# design.net
KiCad netlist of a schematic drawn in Altium Designer
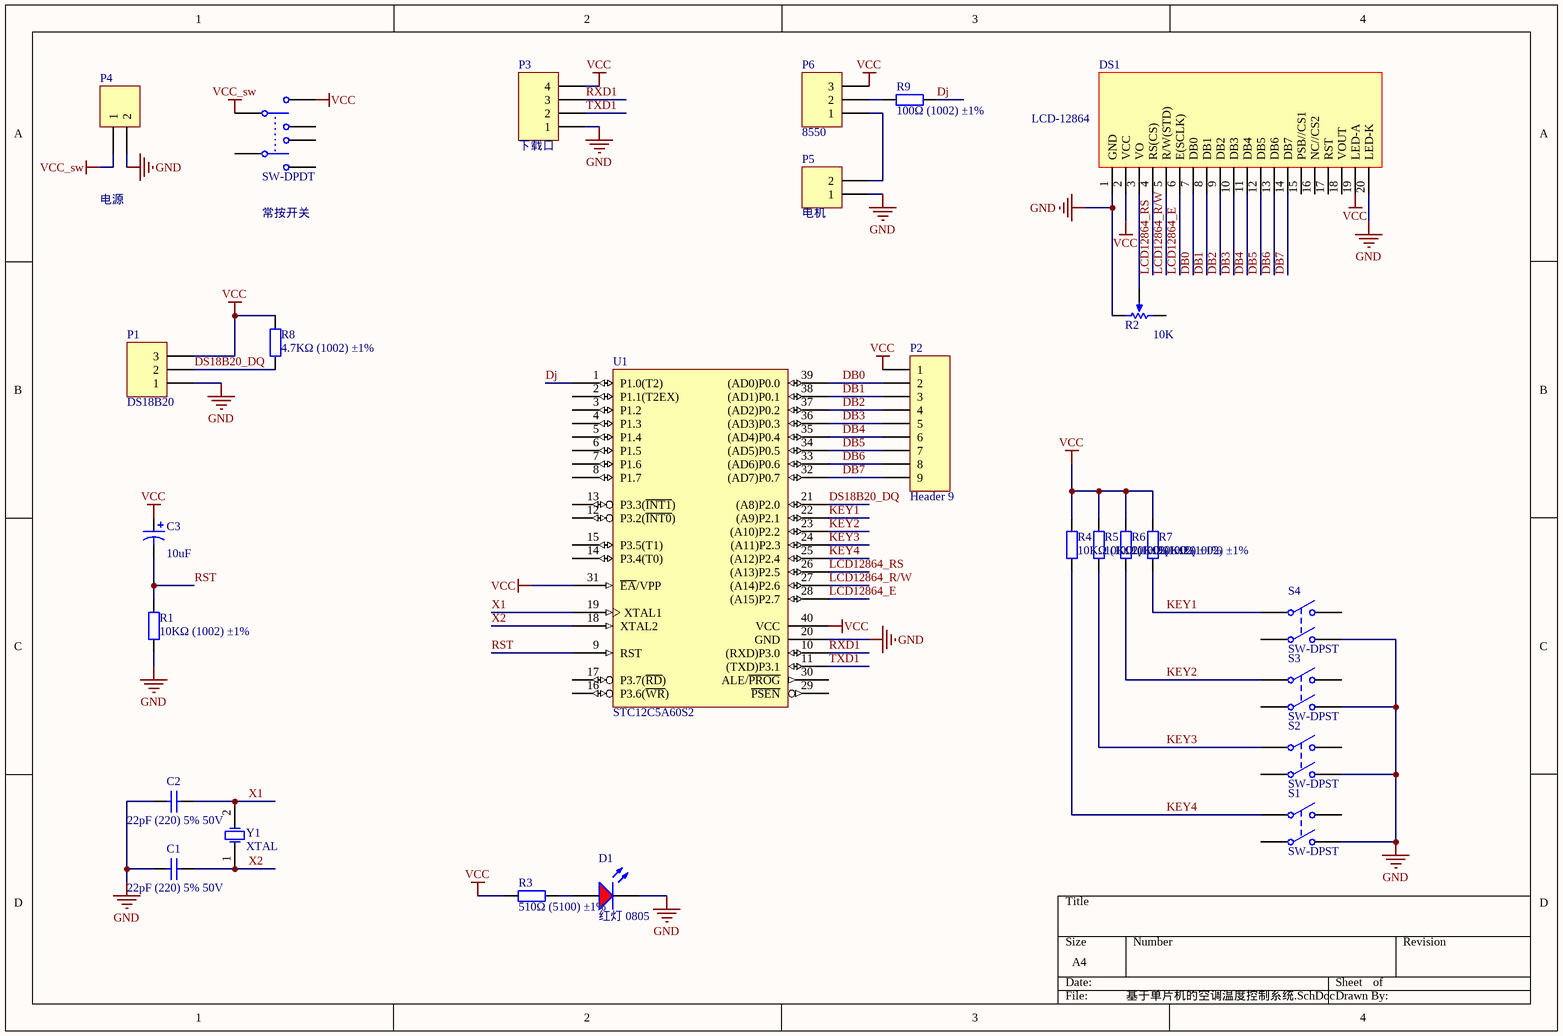
[diagram p0: 基于单片机的空调温度控制系统.SchDoc]

(export (version "E")
  (design (tool "Eeschema 10.0.6"))
  (components
    (comp (ref "C1")
      (value "22pF (220) 5% 50V")
      (footprint "LC-0805_C")
      (description "贴片电容")
      (libsource (lib "Miscellaneous Devices LC") (part "0805 22pF (220) 5% 50V"))
    )
    (comp (ref "C2")
      (value "22pF (220) 5% 50V")
      (footprint "LC-0805_C")
      (description "贴片电容")
      (libsource (lib "Miscellaneous Devices LC") (part "0805 22pF (220) 5% 50V"))
    )
    (comp (ref "C3")
      (value "10uF")
      (footprint "RB.2.5/.6.3mm")
      (description "Polarized Capacitor (Radial)")
      (fields (field (name "Comment") "Cap Pol1") (field (name "PUBLISHER") "Altium Limited"))
      (libsource (lib "Miscellaneous Devices") (part "Cap Pol1"))
    )
    (comp (ref "D1")
      (value "红灯 0805")
      (footprint "LC-0805_LED_S1")
      (description "发光二极管")
      (libsource (lib "Miscellaneous Devices LC") (part "0805 红灯"))
    )
    (comp (ref "DS1")
      (value "LCD-12864")
      (footprint "LCD-12864")
      (description "带//不带字库")
      (libsource (lib "个人") (part "LCD-12864"))
    )
    (comp (ref "P1")
      (value "DS18B20")
      (footprint "HDR1X3")
      (description "Header, 3-Pin")
      (fields (field (name "PUBLISHER") "Altium Limited"))
      (libsource (lib "Miscellaneous Connectors") (part "Header 3"))
    )
    (comp (ref "P2")
      (value "Header 9")
      (footprint "HDR1X9")
      (description "Header, 9-Pin")
      (fields (field (name "PUBLISHER") "Altium Limited"))
      (libsource (lib "Miscellaneous Connectors") (part "Header 9"))
    )
    (comp (ref "P3")
      (value "下载口")
      (footprint "HDR1X4")
      (description "Header, 4-Pin")
      (fields (field (name "PUBLISHER") "Altium Limited"))
      (libsource (lib "Miscellaneous Connectors") (part "Header 4"))
    )
    (comp (ref "P4")
      (value "电源")
      (footprint "DC插座")
      (description "Header, 2-Pin")
      (fields (field (name "PUBLISHER") "Altium Limited"))
      (libsource (lib "Miscellaneous Connectors") (part "Header 2"))
    )
    (comp (ref "P5")
      (value "电机")
      (footprint "HDR1X2")
      (description "Header, 2-Pin")
      (fields (field (name "PUBLISHER") "Altium Limited"))
      (libsource (lib "") (part "Header 2_1"))
    )
    (comp (ref "P6")
      (value "8550")
      (footprint "HDR1X3")
      (description "Header, 3-Pin")
      (fields (field (name "PUBLISHER") "Altium Limited"))
      (libsource (lib "Miscellaneous Connectors") (part "Header 3"))
    )
    (comp (ref "R1")
      (value "10KΩ (1002) ±1%")
      (footprint "LC-0805_R")
      (description "贴片电阻")
      (libsource (lib "Miscellaneous Devices LC") (part "0805 10KΩ (1002) 1%"))
    )
    (comp (ref "R2")
      (value "10K")
      (footprint "VR5")
      (description "Potentiometer")
      (fields (field (name "Comment") "Pot") (field (name "PUBLISHER") "Altium Limited"))
      (libsource (lib "Miscellaneous Devices") (part "RPot"))
    )
    (comp (ref "R3")
      (value "510Ω (5100) ±1%")
      (footprint "LC-0805_R")
      (description "贴片电阻")
      (libsource (lib "Miscellaneous Devices LC") (part "0805 510Ω (5100) 1%"))
    )
    (comp (ref "R4")
      (value "10KΩ (1002) ±1%")
      (footprint "LC-0805_R")
      (description "贴片电阻")
      (libsource (lib "Miscellaneous Devices LC") (part "0805 10KΩ (1002) 1%"))
    )
    (comp (ref "R5")
      (value "10KΩ (1002) ±1%")
      (footprint "LC-0805_R")
      (description "贴片电阻")
      (libsource (lib "Miscellaneous Devices LC") (part "0805 10KΩ (1002) 1%"))
    )
    (comp (ref "R6")
      (value "10KΩ (1002) ±1%")
      (footprint "LC-0805_R")
      (description "贴片电阻")
      (libsource (lib "Miscellaneous Devices LC") (part "0805 10KΩ (1002) 1%"))
    )
    (comp (ref "R7")
      (value "10KΩ (1002) ±1%")
      (footprint "LC-0805_R")
      (description "贴片电阻")
      (libsource (lib "Miscellaneous Devices LC") (part "0805 10KΩ (1002) 1%"))
    )
    (comp (ref "R8")
      (value "4.7KΩ (1002) ±1%")
      (footprint "LC-0805_R")
      (description "贴片电阻")
      (libsource (lib "Miscellaneous Devices LC") (part "0805 10KΩ (1002) 1%"))
    )
    (comp (ref "R9")
      (value "100Ω (1002) ±1%")
      (footprint "LC-0805_R")
      (description "贴片电阻")
      (libsource (lib "") (part "0805 10KΩ (1002) 1%_1"))
    )
    (comp (ref "S1")
      (value "SW-DPST")
      (footprint "Switch6*6")
      (description "Double-Pole, Single-Throw Switch")
      (fields (field (name "PUBLISHER") "Altium Limited"))
      (libsource (lib "Miscellaneous Devices") (part "SW-DPST"))
    )
    (comp (ref "S2")
      (value "SW-DPST")
      (footprint "Switch6*6")
      (description "Double-Pole, Single-Throw Switch")
      (fields (field (name "PUBLISHER") "Altium Limited"))
      (libsource (lib "Miscellaneous Devices") (part "SW-DPST"))
    )
    (comp (ref "S3")
      (value "SW-DPST")
      (footprint "Switch6*6")
      (description "Double-Pole, Single-Throw Switch")
      (fields (field (name "PUBLISHER") "Altium Limited"))
      (libsource (lib "Miscellaneous Devices") (part "SW-DPST"))
    )
    (comp (ref "S4")
      (value "SW-DPST")
      (footprint "Switch6*6")
      (description "Double-Pole, Single-Throw Switch")
      (fields (field (name "PUBLISHER") "Altium Limited"))
      (libsource (lib "Miscellaneous Devices") (part "SW-DPST"))
    )
    (comp (ref "U1")
      (value "STC12C5A60S2")
      (footprint "DIP40")
      (description "8-Bit Microcontroller with 8K Flash ROM")
      (libsource (lib "Atmel Microcontroller 8051 Architecture") (part "AT89C52"))
    )
    (comp (ref "Y1")
      (value "XTAL")
      (footprint "XTAL")
      (description "Crystal Oscillator")
      (fields (field (name "PUBLISHER") "Altium Limited"))
      (libsource (lib "Miscellaneous Devices") (part "XTAL"))
    )
    (comp (ref "常按开关")
      (value "SW-DPDT")
      (footprint "DPDT-6")
      (description "Double-Pole, Double-Throw Switch")
      (fields (field (name "PUBLISHER") "Altium Limited"))
      (libsource (lib "Miscellaneous Devices") (part "SW-DPDT"))
    )
  )
  (nets
    (net (code "1") (name "/DB0") (class "Default")
      (node (ref "DS1") (pin "7") (pinfunction "DB0_7") (pintype "passive"))
      (node (ref "P2") (pin "2") (pinfunction "2_2") (pintype "passive"))
      (node (ref "U1") (pin "39") (pinfunction "(AD0)P0.0_39") (pintype "bidirectional"))
    )
    (net (code "2") (name "/DB1") (class "Default")
      (node (ref "DS1") (pin "8") (pinfunction "DB1_8") (pintype "passive"))
      (node (ref "P2") (pin "3") (pinfunction "3_3") (pintype "passive"))
      (node (ref "U1") (pin "38") (pinfunction "(AD1)P0.1_38") (pintype "bidirectional"))
    )
    (net (code "3") (name "/DB2") (class "Default")
      (node (ref "DS1") (pin "9") (pinfunction "DB2_9") (pintype "passive"))
      (node (ref "P2") (pin "4") (pinfunction "4_4") (pintype "passive"))
      (node (ref "U1") (pin "37") (pinfunction "(AD2)P0.2_37") (pintype "bidirectional"))
    )
    (net (code "4") (name "/DB3") (class "Default")
      (node (ref "DS1") (pin "10") (pinfunction "DB3_10") (pintype "passive"))
      (node (ref "P2") (pin "5") (pinfunction "5_5") (pintype "passive"))
      (node (ref "U1") (pin "36") (pinfunction "(AD3)P0.3_36") (pintype "bidirectional"))
    )
    (net (code "5") (name "/DB4") (class "Default")
      (node (ref "DS1") (pin "11") (pinfunction "DB4_11") (pintype "passive"))
      (node (ref "P2") (pin "6") (pinfunction "6_6") (pintype "passive"))
      (node (ref "U1") (pin "35") (pinfunction "(AD4)P0.4_35") (pintype "bidirectional"))
    )
    (net (code "6") (name "/DB5") (class "Default")
      (node (ref "DS1") (pin "12") (pinfunction "DB5_12") (pintype "passive"))
      (node (ref "P2") (pin "7") (pinfunction "7_7") (pintype "passive"))
      (node (ref "U1") (pin "34") (pinfunction "(AD5)P0.5_34") (pintype "bidirectional"))
    )
    (net (code "7") (name "/DB6") (class "Default")
      (node (ref "DS1") (pin "13") (pinfunction "DB6_13") (pintype "passive"))
      (node (ref "P2") (pin "8") (pinfunction "8_8") (pintype "passive"))
      (node (ref "U1") (pin "33") (pinfunction "(AD6)P0.6_33") (pintype "bidirectional"))
    )
    (net (code "8") (name "/DB7") (class "Default")
      (node (ref "DS1") (pin "14") (pinfunction "DB7_14") (pintype "passive"))
      (node (ref "P2") (pin "9") (pinfunction "9_9") (pintype "passive"))
      (node (ref "U1") (pin "32") (pinfunction "(AD7)P0.7_32") (pintype "bidirectional"))
    )
    (net (code "9") (name "/DS18B20_DQ") (class "Default")
      (node (ref "P1") (pin "2") (pinfunction "2_2") (pintype "passive"))
      (node (ref "R8") (pin "1") (pinfunction "1_1") (pintype "passive"))
      (node (ref "U1") (pin "21") (pinfunction "(A8)P2.0_21") (pintype "bidirectional"))
    )
    (net (code "10") (name "/Dj") (class "Default")
      (node (ref "R9") (pin "1") (pinfunction "1_1") (pintype "passive"))
      (node (ref "U1") (pin "1") (pinfunction "P1.0(T2)_1") (pintype "bidirectional"))
    )
    (net (code "11") (name "/KEY1") (class "Default")
      (node (ref "R7") (pin "1") (pinfunction "1_1") (pintype "passive"))
      (node (ref "S4") (pin "1") (pinfunction "COMMON1_1") (pintype "passive"))
      (node (ref "U1") (pin "22") (pinfunction "(A9)P2.1_22") (pintype "bidirectional"))
    )
    (net (code "12") (name "/KEY2") (class "Default")
      (node (ref "R6") (pin "1") (pinfunction "1_1") (pintype "passive"))
      (node (ref "S3") (pin "1") (pinfunction "COMMON1_1") (pintype "passive"))
      (node (ref "U1") (pin "23") (pinfunction "(A10)P2.2_23") (pintype "bidirectional"))
    )
    (net (code "13") (name "/KEY3") (class "Default")
      (node (ref "R5") (pin "1") (pinfunction "1_1") (pintype "passive"))
      (node (ref "S2") (pin "1") (pinfunction "COMMON1_1") (pintype "passive"))
      (node (ref "U1") (pin "24") (pinfunction "(A11)P2.3_24") (pintype "bidirectional"))
    )
    (net (code "14") (name "/KEY4") (class "Default")
      (node (ref "R4") (pin "1") (pinfunction "1_1") (pintype "passive"))
      (node (ref "S1") (pin "1") (pinfunction "COMMON1_1") (pintype "passive"))
      (node (ref "U1") (pin "25") (pinfunction "(A12)P2.4_25") (pintype "bidirectional"))
    )
    (net (code "15") (name "/LCD12864_E") (class "Default")
      (node (ref "DS1") (pin "6") (pinfunction "E(SCLK)_6") (pintype "passive"))
      (node (ref "U1") (pin "28") (pinfunction "(A15)P2.7_28") (pintype "bidirectional"))
    )
    (net (code "16") (name "/LCD12864_RS") (class "Default")
      (node (ref "DS1") (pin "4") (pinfunction "RS(CS)_4") (pintype "passive"))
      (node (ref "U1") (pin "26") (pinfunction "(A13)P2.5_26") (pintype "bidirectional"))
    )
    (net (code "17") (name "/LCD12864_R{slash}W") (class "Default")
      (node (ref "DS1") (pin "5") (pinfunction "R/W(STD)_5") (pintype "passive"))
      (node (ref "U1") (pin "27") (pinfunction "(A14)P2.6_27") (pintype "bidirectional"))
    )
    (net (code "18") (name "/RST") (class "Default")
      (node (ref "C3") (pin "2") (pinfunction "2_2") (pintype "passive"))
      (node (ref "R1") (pin "2") (pinfunction "2_2") (pintype "passive"))
      (node (ref "U1") (pin "9") (pinfunction "RST_9") (pintype "input"))
    )
    (net (code "19") (name "/RXD1") (class "Default")
      (node (ref "P3") (pin "3") (pinfunction "3_3") (pintype "passive"))
      (node (ref "U1") (pin "10") (pinfunction "(RXD)P3.0_10") (pintype "bidirectional"))
    )
    (net (code "20") (name "/TXD1") (class "Default")
      (node (ref "P3") (pin "2") (pinfunction "2_2") (pintype "passive"))
      (node (ref "U1") (pin "11") (pinfunction "(TXD)P3.1_11") (pintype "bidirectional"))
    )
    (net (code "21") (name "/X1") (class "Default")
      (node (ref "C2") (pin "2") (pinfunction "2_2") (pintype "passive"))
      (node (ref "U1") (pin "19") (pinfunction "XTAL1_19") (pintype "input"))
      (node (ref "Y1") (pin "2") (pinfunction "OSC2_2") (pintype "passive"))
    )
    (net (code "22") (name "/X2") (class "Default")
      (node (ref "C1") (pin "2") (pinfunction "2_2") (pintype "passive"))
      (node (ref "U1") (pin "18") (pinfunction "XTAL2_18") (pintype "input"))
      (node (ref "Y1") (pin "1") (pinfunction "OSC1_1") (pintype "passive"))
    )
    (net (code "23") (name "GND") (class "Default")
      (node (ref "C1") (pin "1") (pinfunction "1_1") (pintype "passive"))
      (node (ref "C2") (pin "1") (pinfunction "1_1") (pintype "passive"))
      (node (ref "D1") (pin "K") (pinfunction "K_K") (pintype "passive"))
      (node (ref "DS1") (pin "1") (pinfunction "GND_1") (pintype "passive"))
      (node (ref "DS1") (pin "20") (pinfunction "LED-K_20") (pintype "passive"))
      (node (ref "P1") (pin "1") (pinfunction "1_1") (pintype "passive"))
      (node (ref "P3") (pin "1") (pinfunction "1_1") (pintype "passive"))
      (node (ref "P4") (pin "2") (pinfunction "2_2") (pintype "passive"))
      (node (ref "P5") (pin "1") (pinfunction "1_1") (pintype "passive"))
      (node (ref "R1") (pin "1") (pinfunction "1_1") (pintype "passive"))
      (node (ref "R2") (pin "2") (pinfunction "BOT_2") (pintype "passive"))
      (node (ref "S1") (pin "4") (pinfunction "NO2_4") (pintype "passive"))
      (node (ref "S2") (pin "4") (pinfunction "NO2_4") (pintype "passive"))
      (node (ref "S3") (pin "4") (pinfunction "NO2_4") (pintype "passive"))
      (node (ref "S4") (pin "4") (pinfunction "NO2_4") (pintype "passive"))
      (node (ref "U1") (pin "20") (pinfunction "GND_20") (pintype "power_in"))
    )
    (net (code "24") (name "Net-(D1-PadA)") (class "Default")
      (node (ref "D1") (pin "A") (pinfunction "A_A") (pintype "passive"))
      (node (ref "R3") (pin "2") (pinfunction "2_2") (pintype "passive"))
    )
    (net (code "25") (name "Net-(DS1-VO)") (class "Default")
      (node (ref "DS1") (pin "3") (pinfunction "VO_3") (pintype "passive"))
      (node (ref "R2") (pin "3") (pinfunction "TAP_3") (pintype "passive"))
    )
    (net (code "26") (name "Net-(P5-Pad2)") (class "Default")
      (node (ref "P5") (pin "2") (pinfunction "2_2") (pintype "passive"))
      (node (ref "P6") (pin "1") (pinfunction "1_1") (pintype "passive"))
    )
    (net (code "27") (name "Net-(P6-Pad2)") (class "Default")
      (node (ref "P6") (pin "2") (pinfunction "2_2") (pintype "passive"))
      (node (ref "R9") (pin "2") (pinfunction "2_2") (pintype "passive"))
    )
    (net (code "28") (name "VCC") (class "Default")
      (node (ref "C3") (pin "1") (pinfunction "1_1") (pintype "passive"))
      (node (ref "DS1") (pin "19") (pinfunction "LED-A_19") (pintype "passive"))
      (node (ref "DS1") (pin "2") (pinfunction "VCC_2") (pintype "passive"))
      (node (ref "P1") (pin "3") (pinfunction "3_3") (pintype "passive"))
      (node (ref "P2") (pin "1") (pinfunction "1_1") (pintype "passive"))
      (node (ref "P3") (pin "4") (pinfunction "4_4") (pintype "passive"))
      (node (ref "P6") (pin "3") (pinfunction "3_3") (pintype "passive"))
      (node (ref "R3") (pin "1") (pinfunction "1_1") (pintype "passive"))
      (node (ref "R4") (pin "2") (pinfunction "2_2") (pintype "passive"))
      (node (ref "R5") (pin "2") (pinfunction "2_2") (pintype "passive"))
      (node (ref "R6") (pin "2") (pinfunction "2_2") (pintype "passive"))
      (node (ref "R7") (pin "2") (pinfunction "2_2") (pintype "passive"))
      (node (ref "R8") (pin "2") (pinfunction "2_2") (pintype "passive"))
      (node (ref "U1") (pin "31") (pinfunction "~{EA}/VPP_31") (pintype "input"))
      (node (ref "U1") (pin "40") (pinfunction "VCC_40") (pintype "power_in"))
      (node (ref "常按开关") (pin "2") (pinfunction "2_2") (pintype "passive"))
    )
    (net (code "29") (name "VCC_sw") (class "Default")
      (node (ref "P4") (pin "1") (pinfunction "1_1") (pintype "passive"))
      (node (ref "常按开关") (pin "1") (pinfunction "1_1") (pintype "passive"))
    )
    (net (code "30") (name "unconnected-(DS1-NC{slash}{slash}CS2-Pad16)") (class "Default")
      (node (ref "DS1") (pin "16") (pinfunction "NC//CS2_16") (pintype "passive"))
    )
    (net (code "31") (name "unconnected-(DS1-PSB{slash}{slash}CS1-Pad15)") (class "Default")
      (node (ref "DS1") (pin "15") (pinfunction "PSB//CS1_15") (pintype "passive"))
    )
    (net (code "32") (name "unconnected-(DS1-RST-Pad17)") (class "Default")
      (node (ref "DS1") (pin "17") (pinfunction "RST_17") (pintype "passive"))
    )
    (net (code "33") (name "unconnected-(DS1-VOUT-Pad18)") (class "Default")
      (node (ref "DS1") (pin "18") (pinfunction "VOUT_18") (pintype "passive"))
    )
    (net (code "34") (name "unconnected-(R2-TOP-Pad1)") (class "Default")
      (node (ref "R2") (pin "1") (pinfunction "TOP_1") (pintype "passive"))
    )
    (net (code "35") (name "unconnected-(S1-COMMON2-Pad3)") (class "Default")
      (node (ref "S1") (pin "3") (pinfunction "COMMON2_3") (pintype "passive"))
    )
    (net (code "36") (name "unconnected-(S1-NO1-Pad2)") (class "Default")
      (node (ref "S1") (pin "2") (pinfunction "NO1_2") (pintype "passive"))
    )
    (net (code "37") (name "unconnected-(S2-COMMON2-Pad3)") (class "Default")
      (node (ref "S2") (pin "3") (pinfunction "COMMON2_3") (pintype "passive"))
    )
    (net (code "38") (name "unconnected-(S2-NO1-Pad2)") (class "Default")
      (node (ref "S2") (pin "2") (pinfunction "NO1_2") (pintype "passive"))
    )
    (net (code "39") (name "unconnected-(S3-COMMON2-Pad3)") (class "Default")
      (node (ref "S3") (pin "3") (pinfunction "COMMON2_3") (pintype "passive"))
    )
    (net (code "40") (name "unconnected-(S3-NO1-Pad2)") (class "Default")
      (node (ref "S3") (pin "2") (pinfunction "NO1_2") (pintype "passive"))
    )
    (net (code "41") (name "unconnected-(S4-COMMON2-Pad3)") (class "Default")
      (node (ref "S4") (pin "3") (pinfunction "COMMON2_3") (pintype "passive"))
    )
    (net (code "42") (name "unconnected-(S4-NO1-Pad2)") (class "Default")
      (node (ref "S4") (pin "2") (pinfunction "NO1_2") (pintype "passive"))
    )
    (net (code "43") (name "unconnected-(U1-ALE{slash}~{PROG}-Pad30)") (class "Default")
      (node (ref "U1") (pin "30") (pinfunction "ALE/~{PROG}_30") (pintype "output"))
    )
    (net (code "44") (name "unconnected-(U1-P1.1(T2EX)-Pad2)") (class "Default")
      (node (ref "U1") (pin "2") (pinfunction "P1.1(T2EX)_2") (pintype "bidirectional"))
    )
    (net (code "45") (name "unconnected-(U1-P1.2-Pad3)") (class "Default")
      (node (ref "U1") (pin "3") (pinfunction "P1.2_3") (pintype "bidirectional"))
    )
    (net (code "46") (name "unconnected-(U1-P1.3-Pad4)") (class "Default")
      (node (ref "U1") (pin "4") (pinfunction "P1.3_4") (pintype "bidirectional"))
    )
    (net (code "47") (name "unconnected-(U1-P1.4-Pad5)") (class "Default")
      (node (ref "U1") (pin "5") (pinfunction "P1.4_5") (pintype "bidirectional"))
    )
    (net (code "48") (name "unconnected-(U1-P1.5-Pad6)") (class "Default")
      (node (ref "U1") (pin "6") (pinfunction "P1.5_6") (pintype "bidirectional"))
    )
    (net (code "49") (name "unconnected-(U1-P1.6-Pad7)") (class "Default")
      (node (ref "U1") (pin "7") (pinfunction "P1.6_7") (pintype "bidirectional"))
    )
    (net (code "50") (name "unconnected-(U1-P1.7-Pad8)") (class "Default")
      (node (ref "U1") (pin "8") (pinfunction "P1.7_8") (pintype "bidirectional"))
    )
    (net (code "51") (name "unconnected-(U1-P3.2(~{INT0})-Pad12)") (class "Default")
      (node (ref "U1") (pin "12") (pinfunction "P3.2(~{INT0})_12") (pintype "bidirectional"))
    )
    (net (code "52") (name "unconnected-(U1-P3.3(~{INT1})-Pad13)") (class "Default")
      (node (ref "U1") (pin "13") (pinfunction "P3.3(~{INT1})_13") (pintype "bidirectional"))
    )
    (net (code "53") (name "unconnected-(U1-P3.4(T0)-Pad14)") (class "Default")
      (node (ref "U1") (pin "14") (pinfunction "P3.4(T0)_14") (pintype "bidirectional"))
    )
    (net (code "54") (name "unconnected-(U1-P3.5(T1)-Pad15)") (class "Default")
      (node (ref "U1") (pin "15") (pinfunction "P3.5(T1)_15") (pintype "bidirectional"))
    )
    (net (code "55") (name "unconnected-(U1-P3.6(~{WR})-Pad16)") (class "Default")
      (node (ref "U1") (pin "16") (pinfunction "P3.6(~{WR})_16") (pintype "bidirectional"))
    )
    (net (code "56") (name "unconnected-(U1-P3.7(~{RD})-Pad17)") (class "Default")
      (node (ref "U1") (pin "17") (pinfunction "P3.7(~{RD})_17") (pintype "bidirectional"))
    )
    (net (code "57") (name "unconnected-(U1-~{PSEN}-Pad29)") (class "Default")
      (node (ref "U1") (pin "29") (pinfunction "~{PSEN}_29") (pintype "output"))
    )
    (net (code "58") (name "unconnected-(常按开关-Pad3)") (class "Default")
      (node (ref "常按开关") (pin "3") (pinfunction "3_3") (pintype "passive"))
    )
    (net (code "59") (name "unconnected-(常按开关-Pad4)") (class "Default")
      (node (ref "常按开关") (pin "4") (pinfunction "4_4") (pintype "passive"))
    )
    (net (code "60") (name "unconnected-(常按开关-Pad5)") (class "Default")
      (node (ref "常按开关") (pin "5") (pinfunction "5_5") (pintype "passive"))
    )
    (net (code "61") (name "unconnected-(常按开关-Pad6)") (class "Default")
      (node (ref "常按开关") (pin "6") (pinfunction "6_6") (pintype "passive"))
    )
  )
)
